# 10_1.net
KiCad netlist of a schematic drawn in EasyEDA
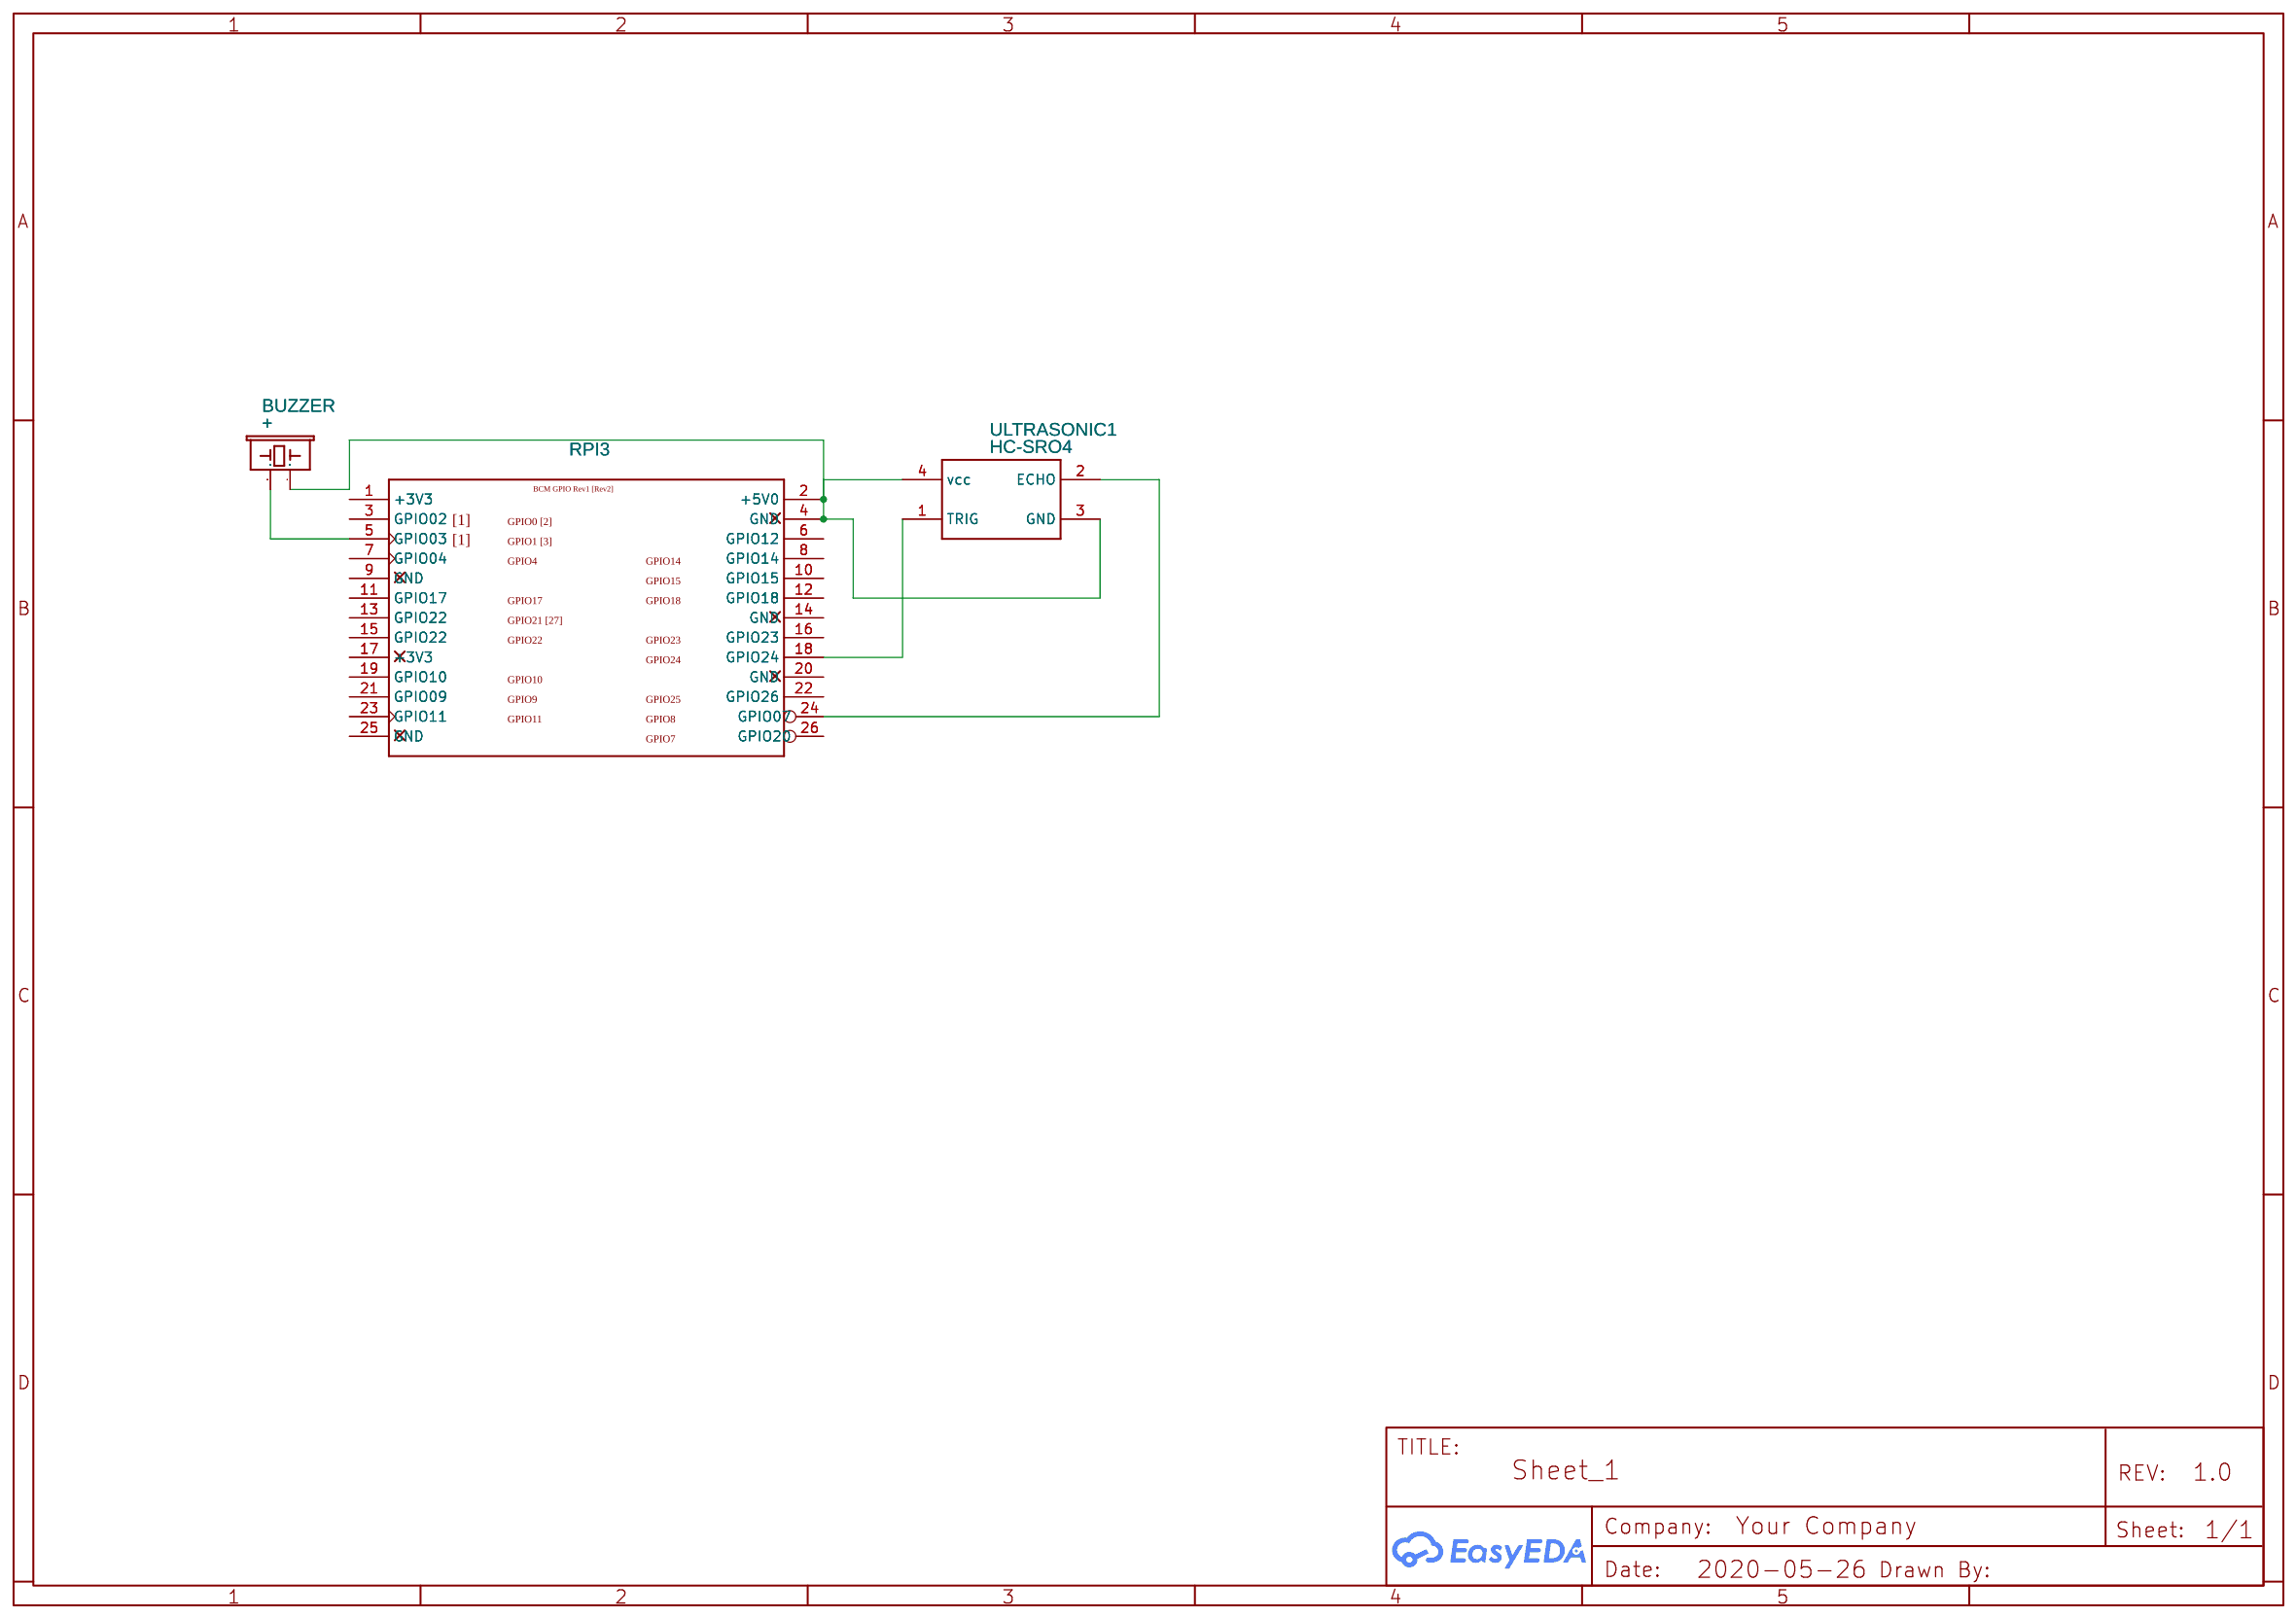
[diagram p0: schematic sheet]

(export (version "E")
  (design (tool "Eeschema 10.0.6"))
  (components
    (comp (ref "BUZZER") (value "+") (libsource (lib "") (part "BUZZER")))
    (comp (ref "RPI3") (value "PI-GPIO-CONNECTOR-SMT") (libsource (lib "") (part "PI-GPIO-CONNECTOR-SMT")))
    (comp (ref "ULTRASONIC1") (value "HC-SRO4") (libsource (lib "") (part "SPM0204UD5SMD")))
  )
  (nets
    (net (code "1") (name "Net-(BUZZER-1)") (class "Default")
      (node (ref "BUZZER") (pin "+") (pinfunction "1_+") (pintype "unspecified"))
      (node (ref "RPI3") (pin "5") (pinfunction "GPIO03_5") (pintype "unspecified"))
    )
    (net (code "2") (name "Net-(BUZZER-2)") (class "Default")
      (node (ref "BUZZER") (pin "-") (pinfunction "2_-") (pintype "unspecified"))
      (node (ref "RPI3") (pin "2") (pinfunction "+5V0_2") (pintype "passive"))
      (node (ref "RPI3") (pin "4") (pinfunction "GND_4") (pintype "unspecified"))
      (node (ref "ULTRASONIC1") (pin "3") (pinfunction "GND_3") (pintype "unspecified"))
      (node (ref "ULTRASONIC1") (pin "4") (pinfunction "vcc_4") (pintype "unspecified"))
    )
    (net (code "3") (name "Net-(RPI3-GPIO07)") (class "Default")
      (node (ref "RPI3") (pin "24") (pinfunction "GPIO07_24") (pintype "unspecified"))
      (node (ref "ULTRASONIC1") (pin "2") (pinfunction "ECHO_2") (pintype "unspecified"))
    )
    (net (code "4") (name "Net-(RPI3-GPIO24)") (class "Default")
      (node (ref "RPI3") (pin "18") (pinfunction "GPIO24_18") (pintype "unspecified"))
      (node (ref "ULTRASONIC1") (pin "1") (pinfunction "TRIG_1") (pintype "unspecified"))
    )
    (net (code "5") (name "unconnected-(RPI3-+3V3-Pad1)") (class "Default")
      (node (ref "RPI3") (pin "1") (pinfunction "+3V3_1") (pintype "passive"))
    )
    (net (code "6") (name "unconnected-(RPI3-+3V3-Pad17)") (class "Default")
      (node (ref "RPI3") (pin "17") (pinfunction "+3V3_17") (pintype "unspecified"))
    )
    (net (code "7") (name "unconnected-(RPI3-GND-Pad9)") (class "Default")
      (node (ref "RPI3") (pin "9") (pinfunction "GND_9") (pintype "unspecified"))
    )
    (net (code "8") (name "unconnected-(RPI3-GND-Pad14)") (class "Default")
      (node (ref "RPI3") (pin "14") (pinfunction "GND_14") (pintype "unspecified"))
    )
    (net (code "9") (name "unconnected-(RPI3-GND-Pad20)") (class "Default")
      (node (ref "RPI3") (pin "20") (pinfunction "GND_20") (pintype "unspecified"))
    )
    (net (code "10") (name "unconnected-(RPI3-GND-Pad25)") (class "Default")
      (node (ref "RPI3") (pin "25") (pinfunction "GND_25") (pintype "unspecified"))
    )
    (net (code "11") (name "unconnected-(RPI3-GPIO02-Pad3)") (class "Default")
      (node (ref "RPI3") (pin "3") (pinfunction "GPIO02_3") (pintype "unspecified"))
    )
    (net (code "12") (name "unconnected-(RPI3-GPIO04-Pad7)") (class "Default")
      (node (ref "RPI3") (pin "7") (pinfunction "GPIO04_7") (pintype "unspecified"))
    )
    (net (code "13") (name "unconnected-(RPI3-GPIO09-Pad21)") (class "Default")
      (node (ref "RPI3") (pin "21") (pinfunction "GPIO09_21") (pintype "unspecified"))
    )
    (net (code "14") (name "unconnected-(RPI3-GPIO10-Pad19)") (class "Default")
      (node (ref "RPI3") (pin "19") (pinfunction "GPIO10_19") (pintype "unspecified"))
    )
    (net (code "15") (name "unconnected-(RPI3-GPIO11-Pad23)") (class "Default")
      (node (ref "RPI3") (pin "23") (pinfunction "GPIO11_23") (pintype "unspecified"))
    )
    (net (code "16") (name "unconnected-(RPI3-GPIO12-Pad6)") (class "Default")
      (node (ref "RPI3") (pin "6") (pinfunction "GPIO12_6") (pintype "passive"))
    )
    (net (code "17") (name "unconnected-(RPI3-GPIO14-Pad8)") (class "Default")
      (node (ref "RPI3") (pin "8") (pinfunction "GPIO14_8") (pintype "unspecified"))
    )
    (net (code "18") (name "unconnected-(RPI3-GPIO15-Pad10)") (class "Default")
      (node (ref "RPI3") (pin "10") (pinfunction "GPIO15_10") (pintype "unspecified"))
    )
    (net (code "19") (name "unconnected-(RPI3-GPIO17-Pad11)") (class "Default")
      (node (ref "RPI3") (pin "11") (pinfunction "GPIO17_11") (pintype "unspecified"))
    )
    (net (code "20") (name "unconnected-(RPI3-GPIO18-Pad12)") (class "Default")
      (node (ref "RPI3") (pin "12") (pinfunction "GPIO18_12") (pintype "unspecified"))
    )
    (net (code "21") (name "unconnected-(RPI3-GPIO20-Pad26)") (class "Default")
      (node (ref "RPI3") (pin "26") (pinfunction "GPIO20_26") (pintype "unspecified"))
    )
    (net (code "22") (name "unconnected-(RPI3-GPIO22-Pad13)") (class "Default")
      (node (ref "RPI3") (pin "13") (pinfunction "GPIO22_13") (pintype "unspecified"))
    )
    (net (code "23") (name "unconnected-(RPI3-GPIO22-Pad15)") (class "Default")
      (node (ref "RPI3") (pin "15") (pinfunction "GPIO22_15") (pintype "unspecified"))
    )
    (net (code "24") (name "unconnected-(RPI3-GPIO23-Pad16)") (class "Default")
      (node (ref "RPI3") (pin "16") (pinfunction "GPIO23_16") (pintype "unspecified"))
    )
    (net (code "25") (name "unconnected-(RPI3-GPIO26-Pad22)") (class "Default")
      (node (ref "RPI3") (pin "22") (pinfunction "GPIO26_22") (pintype "unspecified"))
    )
  )
)
